# medusa-ai-power.net
KiCad netlist of a schematic drawn in Altium Designer
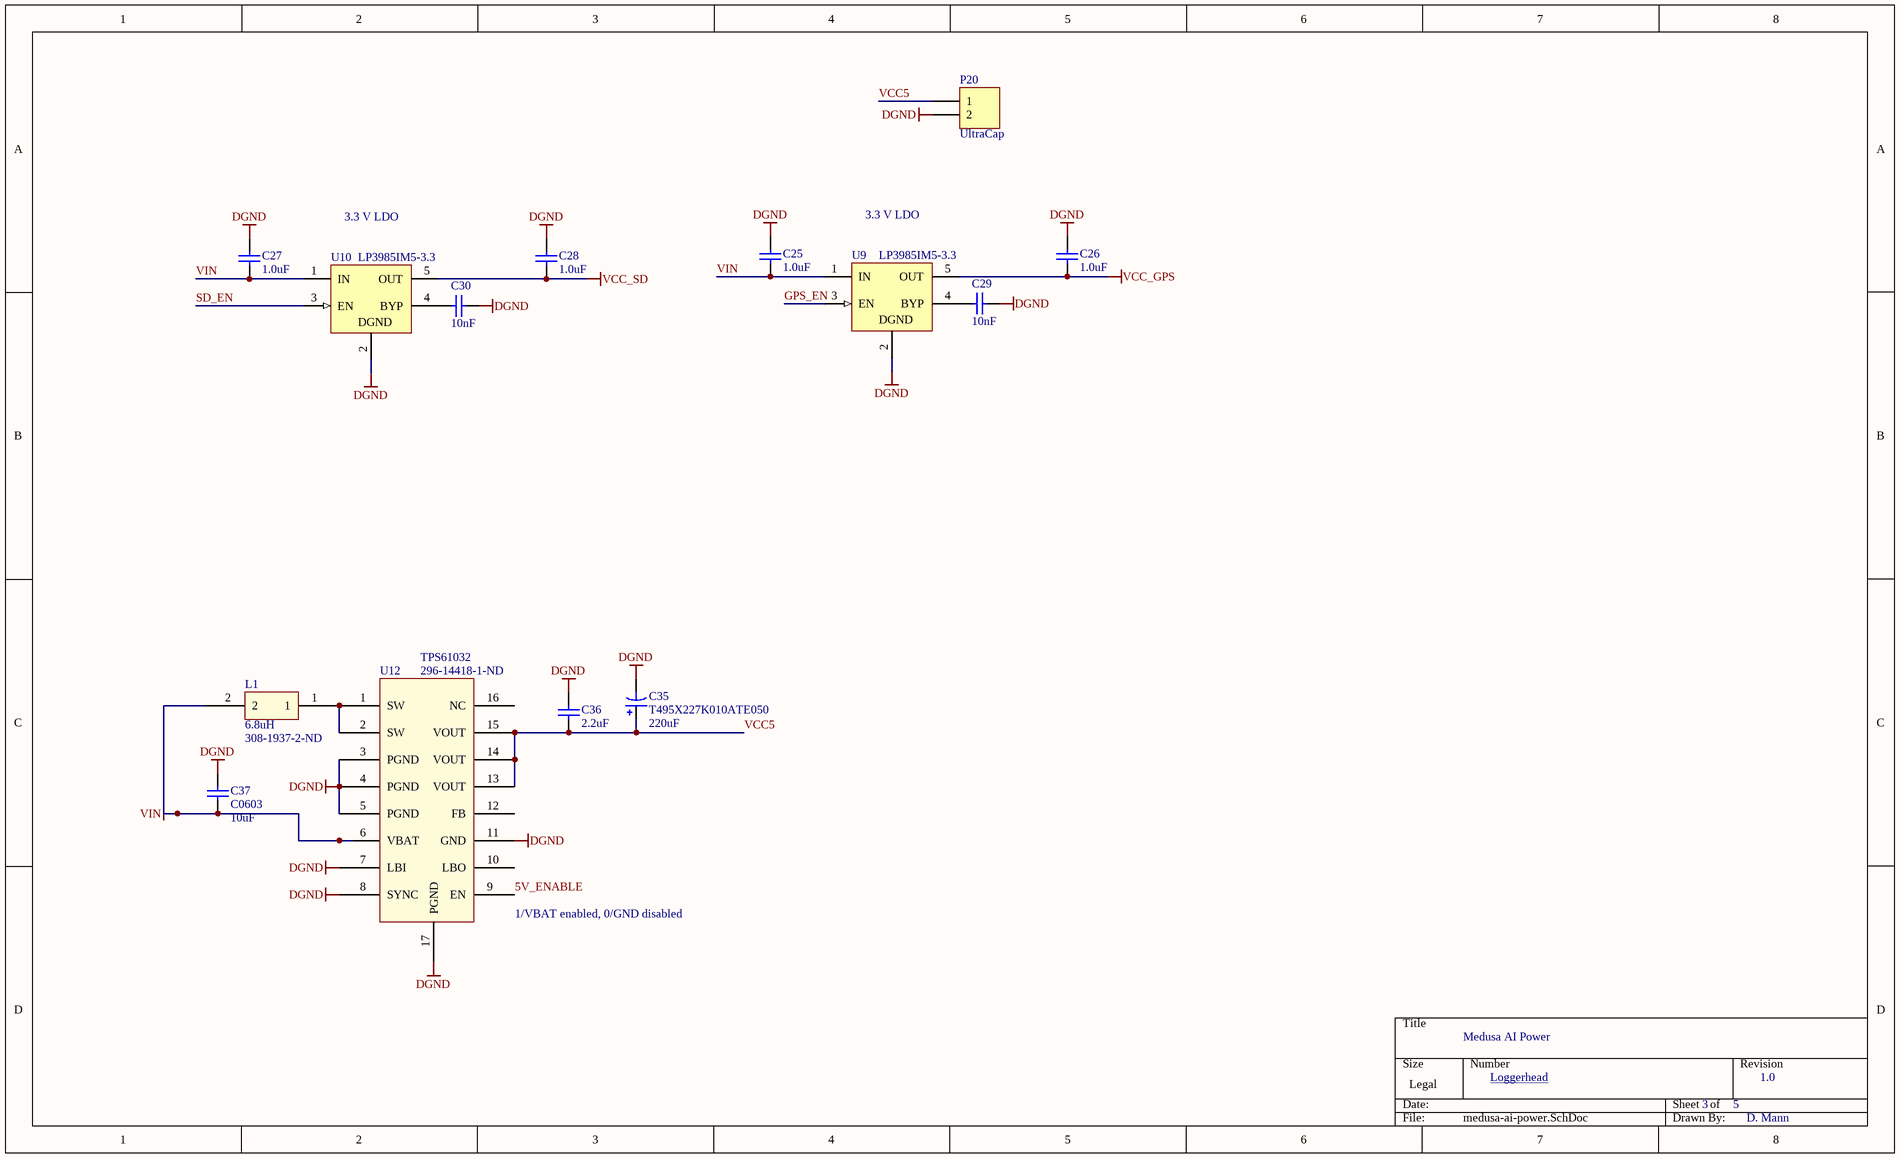
[diagram p0: medusa-ai-power.SchDoc]

(export (version "E")
  (design (tool "Eeschema 10.0.6"))
  (components
    (comp (ref "C25")
      (value "1.0uF")
      (footprint "0402")
      (description "Ceramic Chip Capacitor - Standard")
      (fields (field (name "PUBLISHER") "Altium Limited"))
      (libsource (lib "KEMET Chip Capacitor") (part "C0402"))
    )
    (comp (ref "C26")
      (value "1.0uF")
      (footprint "0402")
      (description "Ceramic Chip Capacitor - Standard")
      (fields (field (name "PUBLISHER") "Altium Limited"))
      (libsource (lib "KEMET Chip Capacitor") (part "C0402"))
    )
    (comp (ref "C27")
      (value "1.0uF")
      (footprint "0402")
      (description "Ceramic Chip Capacitor - Standard")
      (fields (field (name "PUBLISHER") "Altium Limited"))
      (libsource (lib "KEMET Chip Capacitor") (part "C0402"))
    )
    (comp (ref "C28")
      (value "1.0uF")
      (footprint "0402")
      (description "Ceramic Chip Capacitor - Standard")
      (fields (field (name "PUBLISHER") "Altium Limited"))
      (libsource (lib "KEMET Chip Capacitor") (part "C0402"))
    )
    (comp (ref "C29")
      (value "10nF")
      (footprint "0402")
      (description "Ceramic Chip Capacitor - Standard")
      (fields (field (name "PUBLISHER") "Altium Limited"))
      (libsource (lib "KEMET Chip Capacitor") (part "C0402"))
    )
    (comp (ref "C30")
      (value "10nF")
      (footprint "0402")
      (description "Ceramic Chip Capacitor - Standard")
      (fields (field (name "PUBLISHER") "Altium Limited"))
      (libsource (lib "KEMET Chip Capacitor") (part "C0402"))
    )
    (comp (ref "C35")
      (value "T495X227K010ATE050")
      (footprint "X")
      (description "Solid Tantalum Chip Capacitor, Standard T495 Series - Low ESR, Surge Robust")
      (fields (field (name "ALTIUM_VALUE") "220uF") (field (name "PUBLISHER") "Altium Limited"))
      (libsource (lib "KEMET Chip Capacitor") (part "T495X"))
    )
    (comp (ref "C36")
      (value "2.2uF")
      (footprint "0402")
      (description "Ceramic Chip Capacitor - Standard")
      (fields (field (name "PUBLISHER") "Altium Limited"))
      (libsource (lib "KEMET Chip Capacitor") (part "C0402"))
    )
    (comp (ref "C37")
      (value "C0603")
      (footprint "0603")
      (description "Ceramic Chip Capacitor - Standard")
      (fields (field (name "ALTIUM_VALUE") "10uF") (field (name "PUBLISHER") "Altium Limited"))
      (libsource (lib "KEMET Chip Capacitor") (part "C0603"))
    )
    (comp (ref "L1")
      (value "6.8uH")
      (footprint "Inductor - duplicate")
      (description "Sumida Inductor")
      (fields (field (name "SUPPLIER PART NUMBER 1") "308-1937-2-ND"))
      (libsource (lib "Loggerhead") (part "Inductor 6.8uH"))
    )
    (comp (ref "P20")
      (value "UltraCap")
      (footprint "HDR1X2")
      (description "Header, 2-Pin")
      (fields (field (name "PUBLISHER") "Altium Limited"))
      (libsource (lib "Miscellaneous Connectors") (part "Header 2"))
    )
    (comp (ref "U9")
      (value "LP3985IM5-3.3")
      (footprint "MF05A_N")
      (description "Micropower, 150mA Low-Noise Ultra Low-Dropout CMOS Voltage Regulator")
      (fields
        (field (name "MANUFACTURER") "National Semiconductor")
        (field (name "DIGIKEYPARTNUMBER") "LP3985IM5-3.3CT-ND")
        (field (name "PUBLISHER") "Altium Limited")
      )
      (libsource (lib "NSC LDO") (part "LP3985IM5-3.3"))
    )
    (comp (ref "U10")
      (value "LP3985IM5-3.3")
      (footprint "MF05A_N")
      (description "Micropower, 150mA Low-Noise Ultra Low-Dropout CMOS Voltage Regulator")
      (fields
        (field (name "MANUFACTURER") "National Semiconductor")
        (field (name "DIGIKEYPARTNUMBER") "LP3985IM5-3.3CT-ND")
        (field (name "PUBLISHER") "Altium Limited")
      )
      (libsource (lib "NSC LDO") (part "LP3985IM5-3.3"))
    )
    (comp (ref "U12")
      (value "TPS61032")
      (footprint "TPS6103x")
      (description "Boost converter")
      (fields (field (name "SUPPLIER PART NUMBER 2") "296-14418-1-ND"))
      (libsource (lib "Loggerhead") (part "TPS6103x"))
    )
  )
  (nets
    (net (code "1") (name "/5V_ENABLE") (class "Default")
      (node (ref "U12") (pin "9") (pinfunction "EN_9") (pintype "passive"))
    )
    (net (code "2") (name "/GPS_EN") (class "Default")
      (node (ref "U9") (pin "3") (pinfunction "EN_3") (pintype "input"))
    )
    (net (code "3") (name "/SD_EN") (class "Default")
      (node (ref "U10") (pin "3") (pinfunction "EN_3") (pintype "input"))
    )
    (net (code "4") (name "/VCC5") (class "Default")
      (node (ref "C35") (pin "1") (pinfunction "1_1") (pintype "passive"))
      (node (ref "C36") (pin "1") (pinfunction "1_1") (pintype "passive"))
      (node (ref "P20") (pin "1") (pinfunction "1_1") (pintype "passive"))
      (node (ref "U12") (pin "13") (pinfunction "VOUT_13") (pintype "passive"))
      (node (ref "U12") (pin "14") (pinfunction "VOUT_14") (pintype "passive"))
      (node (ref "U12") (pin "15") (pinfunction "VOUT_15") (pintype "passive"))
    )
    (net (code "5") (name "DGND") (class "Default")
      (node (ref "C25") (pin "2") (pinfunction "2_2") (pintype "passive"))
      (node (ref "C26") (pin "2") (pinfunction "2_2") (pintype "passive"))
      (node (ref "C27") (pin "2") (pinfunction "2_2") (pintype "passive"))
      (node (ref "C28") (pin "2") (pinfunction "2_2") (pintype "passive"))
      (node (ref "C29") (pin "1") (pinfunction "1_1") (pintype "passive"))
      (node (ref "C30") (pin "1") (pinfunction "1_1") (pintype "passive"))
      (node (ref "C35") (pin "2") (pinfunction "2_2") (pintype "passive"))
      (node (ref "C36") (pin "2") (pinfunction "2_2") (pintype "passive"))
      (node (ref "C37") (pin "1") (pinfunction "1_1") (pintype "passive"))
      (node (ref "P20") (pin "2") (pinfunction "2_2") (pintype "passive"))
      (node (ref "U10") (pin "2") (pinfunction "GND_2") (pintype "power_in"))
      (node (ref "U12") (pin "11") (pinfunction "GND_11") (pintype "passive"))
      (node (ref "U12") (pin "17") (pinfunction "PGND_17") (pintype "passive"))
      (node (ref "U12") (pin "3") (pinfunction "PGND_3") (pintype "passive"))
      (node (ref "U12") (pin "4") (pinfunction "PGND_4") (pintype "passive"))
      (node (ref "U12") (pin "5") (pinfunction "PGND_5") (pintype "passive"))
      (node (ref "U12") (pin "7") (pinfunction "LBI_7") (pintype "passive"))
      (node (ref "U12") (pin "8") (pinfunction "SYNC_8") (pintype "passive"))
      (node (ref "U9") (pin "2") (pinfunction "GND_2") (pintype "power_in"))
    )
    (net (code "6") (name "Net-(L1-Pad1)") (class "Default")
      (node (ref "L1") (pin "1") (pinfunction "1_1") (pintype "passive"))
      (node (ref "U12") (pin "1") (pinfunction "SW_1") (pintype "passive"))
      (node (ref "U12") (pin "2") (pinfunction "SW_2") (pintype "passive"))
    )
    (net (code "7") (name "Net-(U9-BYP)") (class "Default")
      (node (ref "C29") (pin "2") (pinfunction "2_2") (pintype "passive"))
      (node (ref "U9") (pin "4") (pinfunction "BYP_4") (pintype "passive"))
    )
    (net (code "8") (name "Net-(U10-BYP)") (class "Default")
      (node (ref "C30") (pin "2") (pinfunction "2_2") (pintype "passive"))
      (node (ref "U10") (pin "4") (pinfunction "BYP_4") (pintype "passive"))
    )
    (net (code "9") (name "VCC_GPS") (class "Default")
      (node (ref "C26") (pin "1") (pinfunction "1_1") (pintype "passive"))
      (node (ref "U9") (pin "5") (pinfunction "OUT_5") (pintype "power_in"))
    )
    (net (code "10") (name "VCC_SD") (class "Default")
      (node (ref "C28") (pin "1") (pinfunction "1_1") (pintype "passive"))
      (node (ref "U10") (pin "5") (pinfunction "OUT_5") (pintype "power_in"))
    )
    (net (code "11") (name "VIN") (class "Default")
      (node (ref "C25") (pin "1") (pinfunction "1_1") (pintype "passive"))
      (node (ref "C27") (pin "1") (pinfunction "1_1") (pintype "passive"))
      (node (ref "C37") (pin "2") (pinfunction "2_2") (pintype "passive"))
      (node (ref "L1") (pin "2") (pinfunction "2_2") (pintype "passive"))
      (node (ref "U10") (pin "1") (pinfunction "IN_1") (pintype "power_in"))
      (node (ref "U12") (pin "6") (pinfunction "VBAT_6") (pintype "passive"))
      (node (ref "U9") (pin "1") (pinfunction "IN_1") (pintype "power_in"))
    )
    (net (code "12") (name "unconnected-(U12-FB-Pad12)") (class "Default")
      (node (ref "U12") (pin "12") (pinfunction "FB_12") (pintype "passive"))
    )
    (net (code "13") (name "unconnected-(U12-LBO-Pad10)") (class "Default")
      (node (ref "U12") (pin "10") (pinfunction "LBO_10") (pintype "passive"))
    )
    (net (code "14") (name "unconnected-(U12-NC-Pad16)") (class "Default")
      (node (ref "U12") (pin "16") (pinfunction "NC_16") (pintype "passive"))
    )
  )
)
